# LPDDR4_SDRAM_2.net
KiCad netlist of a schematic drawn in Altium Designer
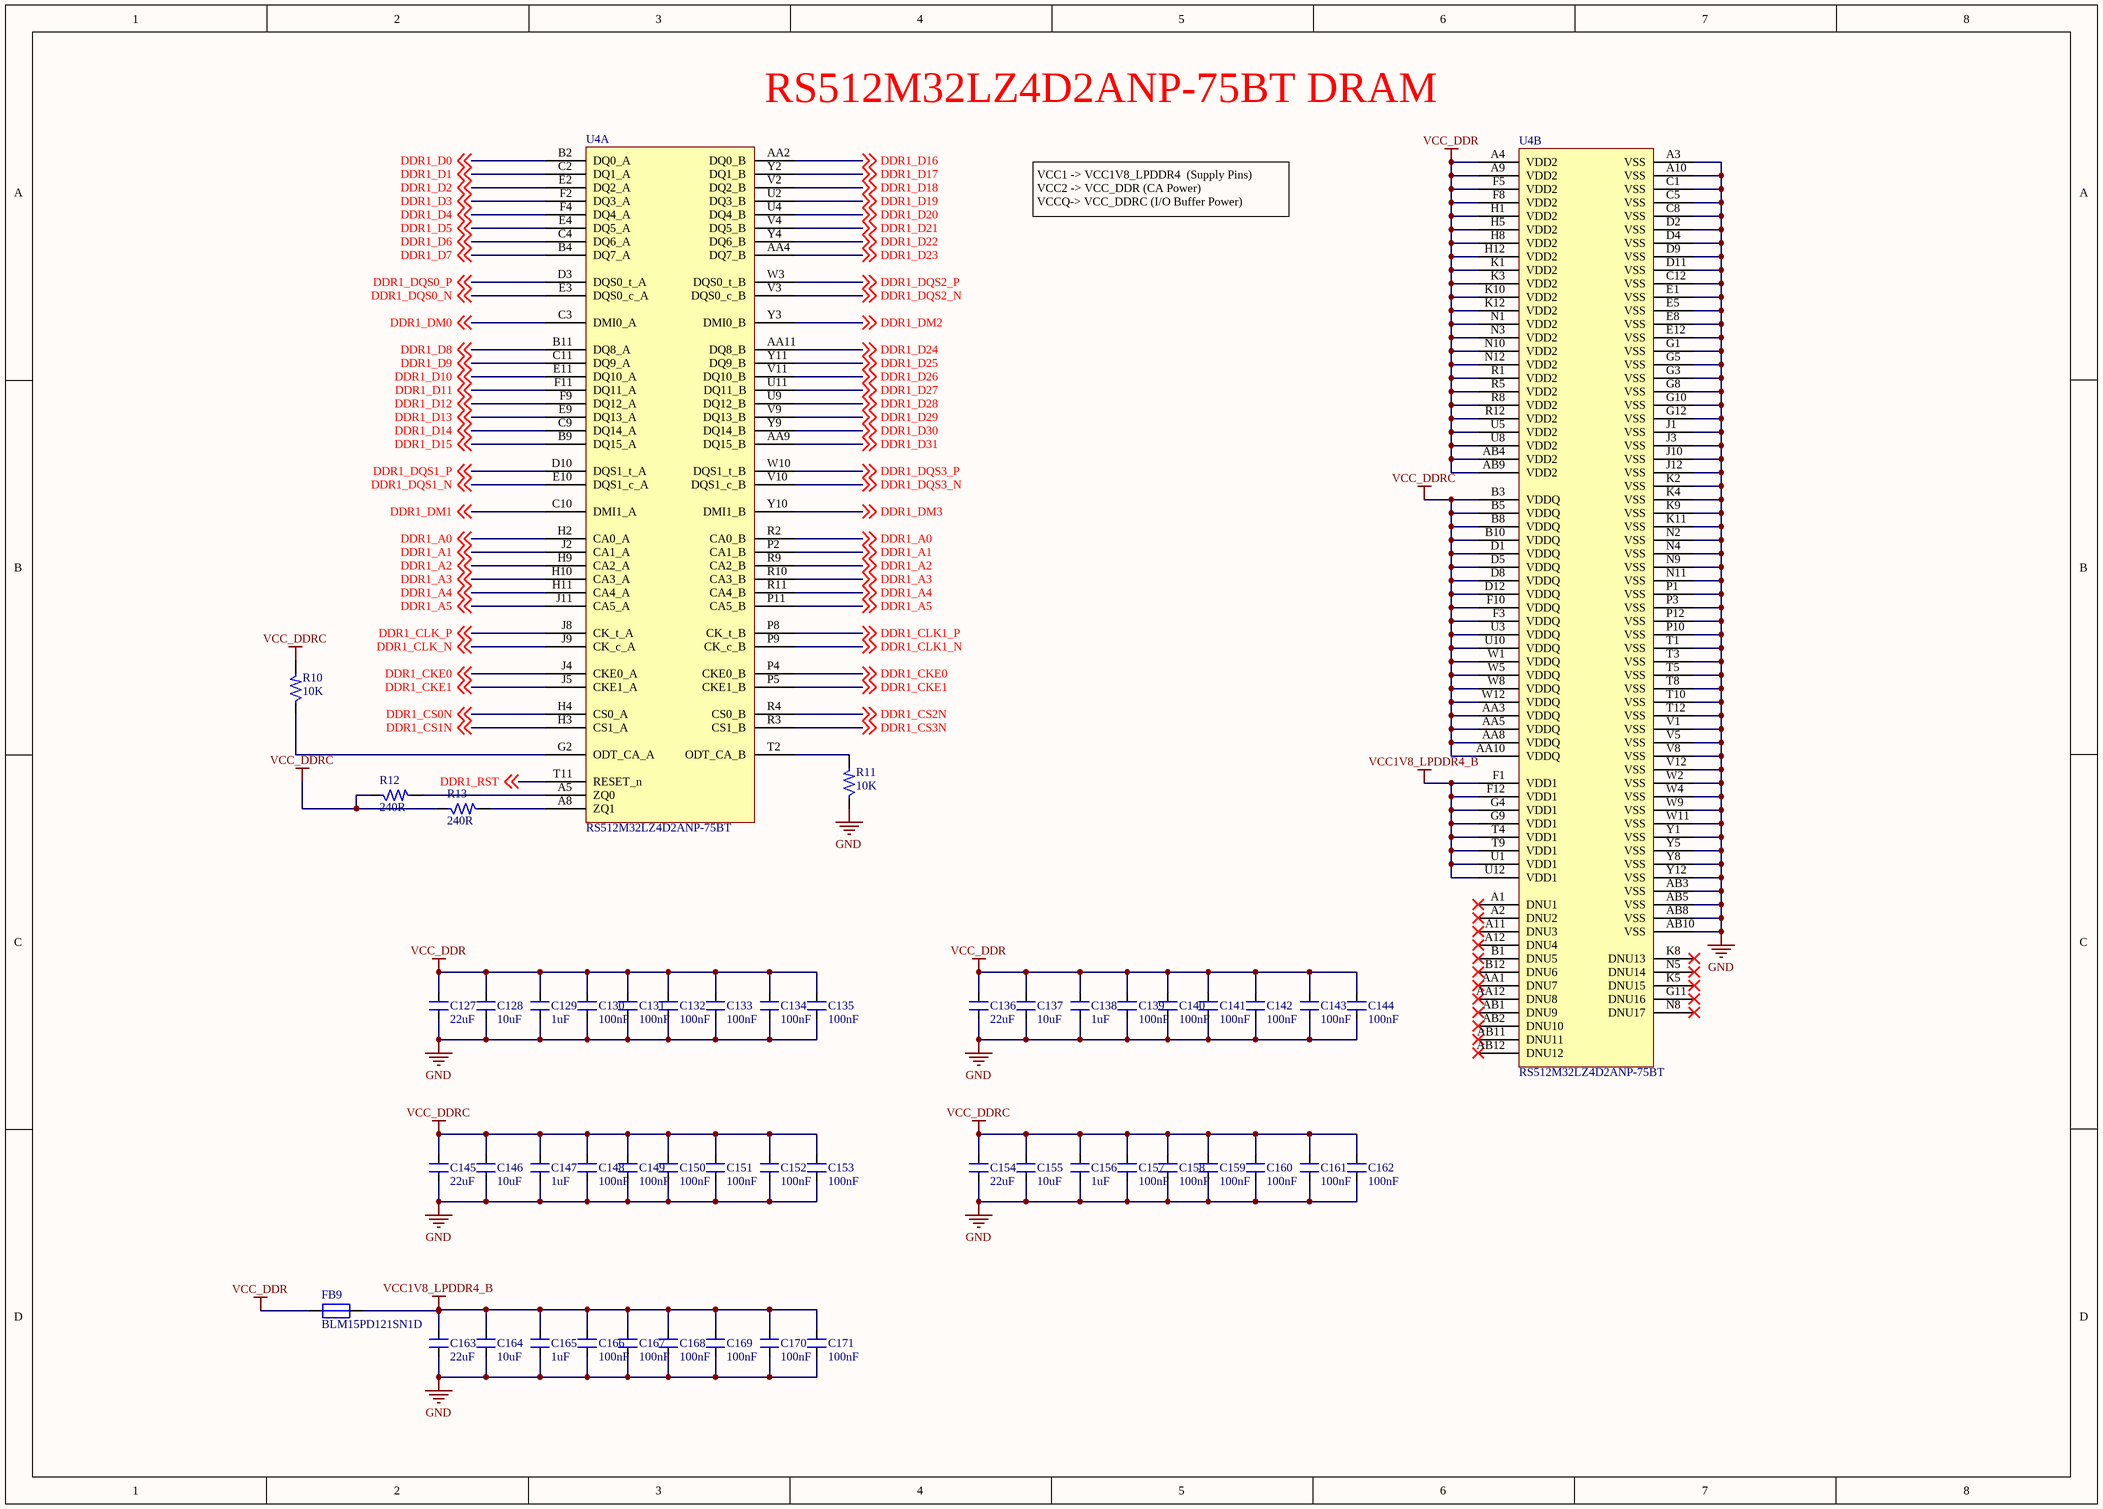
[diagram p0: LPDDR4 SDRAM_2.SchDoc]

(export (version "E")
  (design (tool "Eeschema 10.0.6"))
  (components
    (comp (ref "C127")
      (value "22uF")
      (footprint "CAP_0402")
      (description "22µF ±20% 6.3V Ceramic Capacitor X5R 0402 (1005 Metric)")
      (fields
        (field (name "MANUFACTURER") "Murata Electronics")
        (field (name "MANUFACTURER PART NUMBER") "CL05A226MQ5N6J8")
      )
      (libsource (lib "RK3399 _Module_Intlib") (part "CAP_22uF-6.3V-20%-0402"))
    )
    (comp (ref "C128")
      (value "10uF")
      (footprint "CAP_0402")
      (description "10µF ±20% 10V Ceramic Capacitor X5R 0402 (1005 Metric)")
      (fields
        (field (name "MANUFACTURER PART NUMBER") "CL05A106MP5NUNC")
        (field (name "MANUFACTURER") "Samsung Electro-Mechanics")
      )
      (libsource (lib "RK3399 _Module_Schlib") (part "CAP_10uF-10V-20%-0402"))
    )
    (comp (ref "C129")
      (value "1uF")
      (footprint "CAP_0201")
      (description "1µF ±20% 16V Ceramic Capacitor X5R 0201 (0603 Metric)")
      (fields
        (field (name "MANUFACTURER") "Samsung Electro-Mechanics")
        (field (name "MANUFACTURER PART NUMBER") "CL03A105MO3NRNH")
      )
      (libsource (lib "RK3399 _Module_Intlib") (part "CAP_1uF-16V-10%-0201"))
    )
    (comp (ref "C130")
      (value "100nF")
      (footprint "CAP_0201")
      (description "0.1µF ±10% 25V Ceramic Capacitor X5R 0201 (0603 Metric)")
      (fields
        (field (name "MANUFACTURER") "TDK Corporation")
        (field (name "MANUFACTURER PART NUMBER") "C0603X5R1E104K030BB")
      )
      (libsource (lib "RK3399 _Module_Intlib") (part "CAP_100nF-25V-10%-0201"))
    )
    (comp (ref "C131")
      (value "100nF")
      (footprint "CAP_0201")
      (description "0.1µF ±10% 25V Ceramic Capacitor X5R 0201 (0603 Metric)")
      (fields
        (field (name "MANUFACTURER") "TDK Corporation")
        (field (name "MANUFACTURER PART NUMBER") "C0603X5R1E104K030BB")
      )
      (libsource (lib "RK3399 _Module_Intlib") (part "CAP_100nF-25V-10%-0201"))
    )
    (comp (ref "C132")
      (value "100nF")
      (footprint "CAP_0201")
      (description "0.1µF ±10% 25V Ceramic Capacitor X5R 0201 (0603 Metric)")
      (fields
        (field (name "MANUFACTURER") "TDK Corporation")
        (field (name "MANUFACTURER PART NUMBER") "C0603X5R1E104K030BB")
      )
      (libsource (lib "RK3399 _Module_Intlib") (part "CAP_100nF-25V-10%-0201"))
    )
    (comp (ref "C133")
      (value "100nF")
      (footprint "CAP_0201")
      (description "0.1µF ±10% 25V Ceramic Capacitor X5R 0201 (0603 Metric)")
      (fields
        (field (name "MANUFACTURER") "TDK Corporation")
        (field (name "MANUFACTURER PART NUMBER") "C0603X5R1E104K030BB")
      )
      (libsource (lib "RK3399 _Module_Intlib") (part "CAP_100nF-25V-10%-0201"))
    )
    (comp (ref "C134")
      (value "100nF")
      (footprint "CAP_0201")
      (description "0.1µF ±10% 25V Ceramic Capacitor X5R 0201 (0603 Metric)")
      (fields
        (field (name "MANUFACTURER") "TDK Corporation")
        (field (name "MANUFACTURER PART NUMBER") "C0603X5R1E104K030BB")
      )
      (libsource (lib "RK3399 _Module_Intlib") (part "CAP_100nF-25V-10%-0201"))
    )
    (comp (ref "C135")
      (value "100nF")
      (footprint "CAP_0201")
      (description "0.1µF ±10% 25V Ceramic Capacitor X5R 0201 (0603 Metric)")
      (fields
        (field (name "MANUFACTURER") "TDK Corporation")
        (field (name "MANUFACTURER PART NUMBER") "C0603X5R1E104K030BB")
      )
      (libsource (lib "RK3399 _Module_Intlib") (part "CAP_100nF-25V-10%-0201"))
    )
    (comp (ref "C136")
      (value "22uF")
      (footprint "CAP_0402")
      (description "22µF ±20% 6.3V Ceramic Capacitor X5R 0402 (1005 Metric)")
      (fields
        (field (name "MANUFACTURER") "Murata Electronics")
        (field (name "MANUFACTURER PART NUMBER") "CL05A226MQ5N6J8")
      )
      (libsource (lib "RK3399 _Module_Intlib") (part "CAP_22uF-6.3V-20%-0402"))
    )
    (comp (ref "C137")
      (value "10uF")
      (footprint "CAP_0402")
      (description "10µF ±20% 10V Ceramic Capacitor X5R 0402 (1005 Metric)")
      (fields
        (field (name "MANUFACTURER PART NUMBER") "CL05A106MP5NUNC")
        (field (name "MANUFACTURER") "Samsung Electro-Mechanics")
      )
      (libsource (lib "RK3399 _Module_Schlib") (part "CAP_10uF-10V-20%-0402"))
    )
    (comp (ref "C138")
      (value "1uF")
      (footprint "CAP_0201")
      (description "1µF ±20% 16V Ceramic Capacitor X5R 0201 (0603 Metric)")
      (fields
        (field (name "MANUFACTURER") "Samsung Electro-Mechanics")
        (field (name "MANUFACTURER PART NUMBER") "CL03A105MO3NRNH")
      )
      (libsource (lib "RK3399 _Module_Intlib") (part "CAP_1uF-16V-10%-0201"))
    )
    (comp (ref "C139")
      (value "100nF")
      (footprint "CAP_0201")
      (description "0.1µF ±10% 25V Ceramic Capacitor X5R 0201 (0603 Metric)")
      (fields
        (field (name "MANUFACTURER") "TDK Corporation")
        (field (name "MANUFACTURER PART NUMBER") "C0603X5R1E104K030BB")
      )
      (libsource (lib "RK3399 _Module_Intlib") (part "CAP_100nF-25V-10%-0201"))
    )
    (comp (ref "C140")
      (value "100nF")
      (footprint "CAP_0201")
      (description "0.1µF ±10% 25V Ceramic Capacitor X5R 0201 (0603 Metric)")
      (fields
        (field (name "MANUFACTURER") "TDK Corporation")
        (field (name "MANUFACTURER PART NUMBER") "C0603X5R1E104K030BB")
      )
      (libsource (lib "RK3399 _Module_Intlib") (part "CAP_100nF-25V-10%-0201"))
    )
    (comp (ref "C141")
      (value "100nF")
      (footprint "CAP_0201")
      (description "0.1µF ±10% 25V Ceramic Capacitor X5R 0201 (0603 Metric)")
      (fields
        (field (name "MANUFACTURER") "TDK Corporation")
        (field (name "MANUFACTURER PART NUMBER") "C0603X5R1E104K030BB")
      )
      (libsource (lib "RK3399 _Module_Intlib") (part "CAP_100nF-25V-10%-0201"))
    )
    (comp (ref "C142")
      (value "100nF")
      (footprint "CAP_0201")
      (description "0.1µF ±10% 25V Ceramic Capacitor X5R 0201 (0603 Metric)")
      (fields
        (field (name "MANUFACTURER") "TDK Corporation")
        (field (name "MANUFACTURER PART NUMBER") "C0603X5R1E104K030BB")
      )
      (libsource (lib "RK3399 _Module_Intlib") (part "CAP_100nF-25V-10%-0201"))
    )
    (comp (ref "C143")
      (value "100nF")
      (footprint "CAP_0201")
      (description "0.1µF ±10% 25V Ceramic Capacitor X5R 0201 (0603 Metric)")
      (fields
        (field (name "MANUFACTURER") "TDK Corporation")
        (field (name "MANUFACTURER PART NUMBER") "C0603X5R1E104K030BB")
      )
      (libsource (lib "RK3399 _Module_Intlib") (part "CAP_100nF-25V-10%-0201"))
    )
    (comp (ref "C144")
      (value "100nF")
      (footprint "CAP_0201")
      (description "0.1µF ±10% 25V Ceramic Capacitor X5R 0201 (0603 Metric)")
      (fields
        (field (name "MANUFACTURER") "TDK Corporation")
        (field (name "MANUFACTURER PART NUMBER") "C0603X5R1E104K030BB")
      )
      (libsource (lib "RK3399 _Module_Intlib") (part "CAP_100nF-25V-10%-0201"))
    )
    (comp (ref "C145")
      (value "22uF")
      (footprint "CAP_0402")
      (description "22µF ±20% 6.3V Ceramic Capacitor X5R 0402 (1005 Metric)")
      (fields
        (field (name "MANUFACTURER") "Murata Electronics")
        (field (name "MANUFACTURER PART NUMBER") "CL05A226MQ5N6J8")
      )
      (libsource (lib "RK3399 _Module_Intlib") (part "CAP_22uF-6.3V-20%-0402"))
    )
    (comp (ref "C146")
      (value "10uF")
      (footprint "CAP_0402")
      (description "10µF ±20% 10V Ceramic Capacitor X5R 0402 (1005 Metric)")
      (fields
        (field (name "MANUFACTURER PART NUMBER") "CL05A106MP5NUNC")
        (field (name "MANUFACTURER") "Samsung Electro-Mechanics")
      )
      (libsource (lib "RK3399 _Module_Schlib") (part "CAP_10uF-10V-20%-0402"))
    )
    (comp (ref "C147")
      (value "1uF")
      (footprint "CAP_0201")
      (description "1µF ±20% 16V Ceramic Capacitor X5R 0201 (0603 Metric)")
      (fields
        (field (name "MANUFACTURER") "Samsung Electro-Mechanics")
        (field (name "MANUFACTURER PART NUMBER") "CL03A105MO3NRNH")
      )
      (libsource (lib "RK3399 _Module_Intlib") (part "CAP_1uF-16V-10%-0201"))
    )
    (comp (ref "C148")
      (value "100nF")
      (footprint "CAP_0201")
      (description "0.1µF ±10% 25V Ceramic Capacitor X5R 0201 (0603 Metric)")
      (fields
        (field (name "MANUFACTURER") "TDK Corporation")
        (field (name "MANUFACTURER PART NUMBER") "C0603X5R1E104K030BB")
      )
      (libsource (lib "RK3399 _Module_Intlib") (part "CAP_100nF-25V-10%-0201"))
    )
    (comp (ref "C149")
      (value "100nF")
      (footprint "CAP_0201")
      (description "0.1µF ±10% 25V Ceramic Capacitor X5R 0201 (0603 Metric)")
      (fields
        (field (name "MANUFACTURER") "TDK Corporation")
        (field (name "MANUFACTURER PART NUMBER") "C0603X5R1E104K030BB")
      )
      (libsource (lib "RK3399 _Module_Intlib") (part "CAP_100nF-25V-10%-0201"))
    )
    (comp (ref "C150")
      (value "100nF")
      (footprint "CAP_0201")
      (description "0.1µF ±10% 25V Ceramic Capacitor X5R 0201 (0603 Metric)")
      (fields
        (field (name "MANUFACTURER") "TDK Corporation")
        (field (name "MANUFACTURER PART NUMBER") "C0603X5R1E104K030BB")
      )
      (libsource (lib "RK3399 _Module_Intlib") (part "CAP_100nF-25V-10%-0201"))
    )
    (comp (ref "C151")
      (value "100nF")
      (footprint "CAP_0201")
      (description "0.1µF ±10% 25V Ceramic Capacitor X5R 0201 (0603 Metric)")
      (fields
        (field (name "MANUFACTURER") "TDK Corporation")
        (field (name "MANUFACTURER PART NUMBER") "C0603X5R1E104K030BB")
      )
      (libsource (lib "RK3399 _Module_Intlib") (part "CAP_100nF-25V-10%-0201"))
    )
    (comp (ref "C152")
      (value "100nF")
      (footprint "CAP_0201")
      (description "0.1µF ±10% 25V Ceramic Capacitor X5R 0201 (0603 Metric)")
      (fields
        (field (name "MANUFACTURER") "TDK Corporation")
        (field (name "MANUFACTURER PART NUMBER") "C0603X5R1E104K030BB")
      )
      (libsource (lib "RK3399 _Module_Intlib") (part "CAP_100nF-25V-10%-0201"))
    )
    (comp (ref "C153")
      (value "100nF")
      (footprint "CAP_0201")
      (description "0.1µF ±10% 25V Ceramic Capacitor X5R 0201 (0603 Metric)")
      (fields
        (field (name "MANUFACTURER") "TDK Corporation")
        (field (name "MANUFACTURER PART NUMBER") "C0603X5R1E104K030BB")
      )
      (libsource (lib "RK3399 _Module_Intlib") (part "CAP_100nF-25V-10%-0201"))
    )
    (comp (ref "C154")
      (value "22uF")
      (footprint "CAP_0402")
      (description "22µF ±20% 6.3V Ceramic Capacitor X5R 0402 (1005 Metric)")
      (fields
        (field (name "MANUFACTURER") "Murata Electronics")
        (field (name "MANUFACTURER PART NUMBER") "CL05A226MQ5N6J8")
      )
      (libsource (lib "RK3399 _Module_Intlib") (part "CAP_22uF-6.3V-20%-0402"))
    )
    (comp (ref "C155")
      (value "10uF")
      (footprint "CAP_0402")
      (description "10µF ±20% 10V Ceramic Capacitor X5R 0402 (1005 Metric)")
      (fields
        (field (name "MANUFACTURER PART NUMBER") "CL05A106MP5NUNC")
        (field (name "MANUFACTURER") "Samsung Electro-Mechanics")
      )
      (libsource (lib "RK3399 _Module_Schlib") (part "CAP_10uF-10V-20%-0402"))
    )
    (comp (ref "C156")
      (value "1uF")
      (footprint "CAP_0201")
      (description "1µF ±20% 16V Ceramic Capacitor X5R 0201 (0603 Metric)")
      (fields
        (field (name "MANUFACTURER") "Samsung Electro-Mechanics")
        (field (name "MANUFACTURER PART NUMBER") "CL03A105MO3NRNH")
      )
      (libsource (lib "RK3399 _Module_Intlib") (part "CAP_1uF-16V-10%-0201"))
    )
    (comp (ref "C157")
      (value "100nF")
      (footprint "CAP_0201")
      (description "0.1µF ±10% 25V Ceramic Capacitor X5R 0201 (0603 Metric)")
      (fields
        (field (name "MANUFACTURER") "TDK Corporation")
        (field (name "MANUFACTURER PART NUMBER") "C0603X5R1E104K030BB")
      )
      (libsource (lib "RK3399 _Module_Intlib") (part "CAP_100nF-25V-10%-0201"))
    )
    (comp (ref "C158")
      (value "100nF")
      (footprint "CAP_0201")
      (description "0.1µF ±10% 25V Ceramic Capacitor X5R 0201 (0603 Metric)")
      (fields
        (field (name "MANUFACTURER") "TDK Corporation")
        (field (name "MANUFACTURER PART NUMBER") "C0603X5R1E104K030BB")
      )
      (libsource (lib "RK3399 _Module_Intlib") (part "CAP_100nF-25V-10%-0201"))
    )
    (comp (ref "C159")
      (value "100nF")
      (footprint "CAP_0201")
      (description "0.1µF ±10% 25V Ceramic Capacitor X5R 0201 (0603 Metric)")
      (fields
        (field (name "MANUFACTURER") "TDK Corporation")
        (field (name "MANUFACTURER PART NUMBER") "C0603X5R1E104K030BB")
      )
      (libsource (lib "RK3399 _Module_Intlib") (part "CAP_100nF-25V-10%-0201"))
    )
    (comp (ref "C160")
      (value "100nF")
      (footprint "CAP_0201")
      (description "0.1µF ±10% 25V Ceramic Capacitor X5R 0201 (0603 Metric)")
      (fields
        (field (name "MANUFACTURER") "TDK Corporation")
        (field (name "MANUFACTURER PART NUMBER") "C0603X5R1E104K030BB")
      )
      (libsource (lib "RK3399 _Module_Intlib") (part "CAP_100nF-25V-10%-0201"))
    )
    (comp (ref "C161")
      (value "100nF")
      (footprint "CAP_0201")
      (description "0.1µF ±10% 25V Ceramic Capacitor X5R 0201 (0603 Metric)")
      (fields
        (field (name "MANUFACTURER") "TDK Corporation")
        (field (name "MANUFACTURER PART NUMBER") "C0603X5R1E104K030BB")
      )
      (libsource (lib "RK3399 _Module_Intlib") (part "CAP_100nF-25V-10%-0201"))
    )
    (comp (ref "C162")
      (value "100nF")
      (footprint "CAP_0201")
      (description "0.1µF ±10% 25V Ceramic Capacitor X5R 0201 (0603 Metric)")
      (fields
        (field (name "MANUFACTURER") "TDK Corporation")
        (field (name "MANUFACTURER PART NUMBER") "C0603X5R1E104K030BB")
      )
      (libsource (lib "RK3399 _Module_Intlib") (part "CAP_100nF-25V-10%-0201"))
    )
    (comp (ref "C163")
      (value "22uF")
      (footprint "CAP_0402")
      (description "22µF ±20% 6.3V Ceramic Capacitor X5R 0402 (1005 Metric)")
      (fields
        (field (name "MANUFACTURER") "Murata Electronics")
        (field (name "MANUFACTURER PART NUMBER") "CL05A226MQ5N6J8")
      )
      (libsource (lib "RK3399 _Module_Intlib") (part "CAP_22uF-6.3V-20%-0402"))
    )
    (comp (ref "C164")
      (value "10uF")
      (footprint "CAP_0402")
      (description "10µF ±20% 10V Ceramic Capacitor X5R 0402 (1005 Metric)")
      (fields
        (field (name "MANUFACTURER PART NUMBER") "CL05A106MP5NUNC")
        (field (name "MANUFACTURER") "Samsung Electro-Mechanics")
      )
      (libsource (lib "RK3399 _Module_Schlib") (part "CAP_10uF-10V-20%-0402"))
    )
    (comp (ref "C165")
      (value "1uF")
      (footprint "CAP_0201")
      (description "1µF ±20% 16V Ceramic Capacitor X5R 0201 (0603 Metric)")
      (fields
        (field (name "MANUFACTURER") "Samsung Electro-Mechanics")
        (field (name "MANUFACTURER PART NUMBER") "CL03A105MO3NRNH")
      )
      (libsource (lib "RK3399 _Module_Intlib") (part "CAP_1uF-16V-10%-0201"))
    )
    (comp (ref "C166")
      (value "100nF")
      (footprint "CAP_0201")
      (description "0.1µF ±10% 25V Ceramic Capacitor X5R 0201 (0603 Metric)")
      (fields
        (field (name "MANUFACTURER") "TDK Corporation")
        (field (name "MANUFACTURER PART NUMBER") "C0603X5R1E104K030BB")
      )
      (libsource (lib "RK3399 _Module_Intlib") (part "CAP_100nF-25V-10%-0201"))
    )
    (comp (ref "C167")
      (value "100nF")
      (footprint "CAP_0201")
      (description "0.1µF ±10% 25V Ceramic Capacitor X5R 0201 (0603 Metric)")
      (fields
        (field (name "MANUFACTURER") "TDK Corporation")
        (field (name "MANUFACTURER PART NUMBER") "C0603X5R1E104K030BB")
      )
      (libsource (lib "RK3399 _Module_Intlib") (part "CAP_100nF-25V-10%-0201"))
    )
    (comp (ref "C168")
      (value "100nF")
      (footprint "CAP_0201")
      (description "0.1µF ±10% 25V Ceramic Capacitor X5R 0201 (0603 Metric)")
      (fields
        (field (name "MANUFACTURER") "TDK Corporation")
        (field (name "MANUFACTURER PART NUMBER") "C0603X5R1E104K030BB")
      )
      (libsource (lib "RK3399 _Module_Intlib") (part "CAP_100nF-25V-10%-0201"))
    )
    (comp (ref "C169")
      (value "100nF")
      (footprint "CAP_0201")
      (description "0.1µF ±10% 25V Ceramic Capacitor X5R 0201 (0603 Metric)")
      (fields
        (field (name "MANUFACTURER") "TDK Corporation")
        (field (name "MANUFACTURER PART NUMBER") "C0603X5R1E104K030BB")
      )
      (libsource (lib "RK3399 _Module_Intlib") (part "CAP_100nF-25V-10%-0201"))
    )
    (comp (ref "C170")
      (value "100nF")
      (footprint "CAP_0201")
      (description "0.1µF ±10% 25V Ceramic Capacitor X5R 0201 (0603 Metric)")
      (fields
        (field (name "MANUFACTURER") "TDK Corporation")
        (field (name "MANUFACTURER PART NUMBER") "C0603X5R1E104K030BB")
      )
      (libsource (lib "RK3399 _Module_Intlib") (part "CAP_100nF-25V-10%-0201"))
    )
    (comp (ref "C171")
      (value "100nF")
      (footprint "CAP_0201")
      (description "0.1µF ±10% 25V Ceramic Capacitor X5R 0201 (0603 Metric)")
      (fields
        (field (name "MANUFACTURER") "TDK Corporation")
        (field (name "MANUFACTURER PART NUMBER") "C0603X5R1E104K030BB")
      )
      (libsource (lib "RK3399 _Module_Intlib") (part "CAP_100nF-25V-10%-0201"))
    )
    (comp (ref "FB9")
      (value "BLM15PD121SN1D")
      (footprint "RES_0402")
      (description "120 Ohms @ 100MHz 1 Power Line Ferrite Bead 0402 (1005 Metric) 1.3A 90mOhm")
      (fields (field (name "MANUFACTURER") "Murata Electronics"))
      (libsource (lib "RK3399 _Module_Schlib") (part "FB_120R-1.3A-100Mhz-0402"))
    )
    (comp (ref "R10")
      (value "10K")
      (footprint "RES_0201")
      (description "10 kOhms ±1% 0.05W, 1/20W Chip Resistor 0201 (0603 Metric) Thick Film")
      (fields
        (field (name "MANUFACTURER") "Stackpole Electronics Inc")
        (field (name "MANUFACTURER PART NUMBER") "RMCF0201FT10K0")
      )
      (libsource (lib "RK3399 _Module_Intlib") (part "RES_10K-0.05W-1%-0201"))
    )
    (comp (ref "R11")
      (value "10K")
      (footprint "RES_0201")
      (description "10 kOhms ±1% 0.05W, 1/20W Chip Resistor 0201 (0603 Metric) Thick Film")
      (fields
        (field (name "MANUFACTURER") "Stackpole Electronics Inc")
        (field (name "MANUFACTURER PART NUMBER") "RMCF0201FT10K0")
      )
      (libsource (lib "RK3399 _Module_Intlib") (part "RES_10K-0.05W-1%-0201"))
    )
    (comp (ref "R12")
      (value "240R")
      (footprint "RES_0201")
      (description "240 Ohms ±1% 0.05W, 1/20W Chip Resistor 0201 (0603 Metric) Thick Film")
      (fields
        (field (name "MANUFACTURER") "Yageo")
        (field (name "MANUFACTURER PART NUMBER") "RC0201FR-07240RL")
      )
      (libsource (lib "RK3399 _Module_Intlib") (part "RES_240R-0.05W-1%-0201"))
    )
    (comp (ref "R13")
      (value "240R")
      (footprint "RES_0201")
      (description "240 Ohms ±1% 0.05W, 1/20W Chip Resistor 0201 (0603 Metric) Thick Film")
      (fields
        (field (name "MANUFACTURER") "Yageo")
        (field (name "MANUFACTURER PART NUMBER") "RC0201FR-07240RL")
      )
      (libsource (lib "RK3399 _Module_Intlib") (part "RES_240R-0.05W-1%-0201"))
    )
    (comp (ref "U4")
      (value "RS512M32LZ4D2ANP-75BT")
      (footprint "FBGA200_SMD")
      (fields (field (name "MANUFACTURER") "RAYSON"))
      (libsource (lib "RK3399 _Module_Schlib") (part "IC_RS512M32LZ4D2ANP-75BT"))
    )
  )
  (nets
    (net (code "1") (name "DDR1_A0") (class "Default")
      (node (ref "U4") (pin "H2") (pinfunction "CA0_A_H2") (pintype "passive"))
      (node (ref "U4") (pin "R2") (pinfunction "CA0_B_R2") (pintype "passive"))
    )
    (net (code "2") (name "DDR1_A1") (class "Default")
      (node (ref "U4") (pin "J2") (pinfunction "CA1_A_J2") (pintype "passive"))
      (node (ref "U4") (pin "P2") (pinfunction "CA1_B_P2") (pintype "passive"))
    )
    (net (code "3") (name "DDR1_A2") (class "Default")
      (node (ref "U4") (pin "H9") (pinfunction "CA2_A_H9") (pintype "passive"))
      (node (ref "U4") (pin "R9") (pinfunction "CA2_B_R9") (pintype "passive"))
    )
    (net (code "4") (name "DDR1_A3") (class "Default")
      (node (ref "U4") (pin "H10") (pinfunction "CA3_A_H10") (pintype "passive"))
      (node (ref "U4") (pin "R10") (pinfunction "CA3_B_R10") (pintype "passive"))
    )
    (net (code "5") (name "DDR1_A4") (class "Default")
      (node (ref "U4") (pin "H11") (pinfunction "CA4_A_H11") (pintype "passive"))
      (node (ref "U4") (pin "R11") (pinfunction "CA4_B_R11") (pintype "passive"))
    )
    (net (code "6") (name "DDR1_A5") (class "Default")
      (node (ref "U4") (pin "J11") (pinfunction "CA5_A_J11") (pintype "passive"))
      (node (ref "U4") (pin "P11") (pinfunction "CA5_B_P11") (pintype "passive"))
    )
    (net (code "7") (name "DDR1_CKE0") (class "Default")
      (node (ref "U4") (pin "J4") (pinfunction "CKE0_A_J4") (pintype "passive"))
      (node (ref "U4") (pin "P4") (pinfunction "CKE0_B_P4") (pintype "passive"))
    )
    (net (code "8") (name "DDR1_CKE1") (class "Default")
      (node (ref "U4") (pin "J5") (pinfunction "CKE1_A_J5") (pintype "passive"))
      (node (ref "U4") (pin "P5") (pinfunction "CKE1_B_P5") (pintype "passive"))
    )
    (net (code "9") (name "DDR1_CLK1_N") (class "Default")
      (node (ref "U4") (pin "P9") (pinfunction "CK_c_B_P9") (pintype "passive"))
    )
    (net (code "10") (name "DDR1_CLK1_P") (class "Default")
      (node (ref "U4") (pin "P8") (pinfunction "CK_t_B_P8") (pintype "passive"))
    )
    (net (code "11") (name "DDR1_CLK_N") (class "Default")
      (node (ref "U4") (pin "J9") (pinfunction "CK_c_A_J9") (pintype "passive"))
    )
    (net (code "12") (name "DDR1_CLK_P") (class "Default")
      (node (ref "U4") (pin "J8") (pinfunction "CK_t_A_J8") (pintype "passive"))
    )
    (net (code "13") (name "DDR1_CS0N") (class "Default")
      (node (ref "U4") (pin "H4") (pinfunction "CS0_A_H4") (pintype "passive"))
    )
    (net (code "14") (name "DDR1_CS1N") (class "Default")
      (node (ref "U4") (pin "H3") (pinfunction "CS1_A_H3") (pintype "passive"))
    )
    (net (code "15") (name "DDR1_CS2N") (class "Default")
      (node (ref "U4") (pin "R4") (pinfunction "CS0_B_R4") (pintype "passive"))
    )
    (net (code "16") (name "DDR1_CS3N") (class "Default")
      (node (ref "U4") (pin "R3") (pinfunction "CS1_B_R3") (pintype "passive"))
    )
    (net (code "17") (name "DDR1_D0") (class "Default")
      (node (ref "U4") (pin "B2") (pinfunction "DQ0_A_B2") (pintype "passive"))
    )
    (net (code "18") (name "DDR1_D1") (class "Default")
      (node (ref "U4") (pin "C2") (pinfunction "DQ1_A_C2") (pintype "passive"))
    )
    (net (code "19") (name "DDR1_D2") (class "Default")
      (node (ref "U4") (pin "E2") (pinfunction "DQ2_A_E2") (pintype "passive"))
    )
    (net (code "20") (name "DDR1_D3") (class "Default")
      (node (ref "U4") (pin "F2") (pinfunction "DQ3_A_F2") (pintype "passive"))
    )
    (net (code "21") (name "DDR1_D4") (class "Default")
      (node (ref "U4") (pin "F4") (pinfunction "DQ4_A_F4") (pintype "passive"))
    )
    (net (code "22") (name "DDR1_D5") (class "Default")
      (node (ref "U4") (pin "E4") (pinfunction "DQ5_A_E4") (pintype "passive"))
    )
    (net (code "23") (name "DDR1_D6") (class "Default")
      (node (ref "U4") (pin "C4") (pinfunction "DQ6_A_C4") (pintype "passive"))
    )
    (net (code "24") (name "DDR1_D7") (class "Default")
      (node (ref "U4") (pin "B4") (pinfunction "DQ7_A_B4") (pintype "passive"))
    )
    (net (code "25") (name "DDR1_D8") (class "Default")
      (node (ref "U4") (pin "B11") (pinfunction "DQ8_A_B11") (pintype "passive"))
    )
    (net (code "26") (name "DDR1_D9") (class "Default")
      (node (ref "U4") (pin "C11") (pinfunction "DQ9_A_C11") (pintype "passive"))
    )
    (net (code "27") (name "DDR1_D10") (class "Default")
      (node (ref "U4") (pin "E11") (pinfunction "DQ10_A_E11") (pintype "passive"))
    )
    (net (code "28") (name "DDR1_D11") (class "Default")
      (node (ref "U4") (pin "F11") (pinfunction "DQ11_A_F11") (pintype "passive"))
    )
    (net (code "29") (name "DDR1_D12") (class "Default")
      (node (ref "U4") (pin "F9") (pinfunction "DQ12_A_F9") (pintype "passive"))
    )
    (net (code "30") (name "DDR1_D13") (class "Default")
      (node (ref "U4") (pin "E9") (pinfunction "DQ13_A_E9") (pintype "passive"))
    )
    (net (code "31") (name "DDR1_D14") (class "Default")
      (node (ref "U4") (pin "C9") (pinfunction "DQ14_A_C9") (pintype "passive"))
    )
    (net (code "32") (name "DDR1_D15") (class "Default")
      (node (ref "U4") (pin "B9") (pinfunction "DQ15_A_B9") (pintype "passive"))
    )
    (net (code "33") (name "DDR1_D16") (class "Default")
      (node (ref "U4") (pin "AA2") (pinfunction "DQ0_B_AA2") (pintype "passive"))
    )
    (net (code "34") (name "DDR1_D17") (class "Default")
      (node (ref "U4") (pin "Y2") (pinfunction "DQ1_B_Y2") (pintype "passive"))
    )
    (net (code "35") (name "DDR1_D18") (class "Default")
      (node (ref "U4") (pin "V2") (pinfunction "DQ2_B_V2") (pintype "passive"))
    )
    (net (code "36") (name "DDR1_D19") (class "Default")
      (node (ref "U4") (pin "U2") (pinfunction "DQ3_B_U2") (pintype "passive"))
    )
    (net (code "37") (name "DDR1_D20") (class "Default")
      (node (ref "U4") (pin "U4") (pinfunction "DQ4_B_U4") (pintype "passive"))
    )
    (net (code "38") (name "DDR1_D21") (class "Default")
      (node (ref "U4") (pin "V4") (pinfunction "DQ5_B_V4") (pintype "passive"))
    )
    (net (code "39") (name "DDR1_D22") (class "Default")
      (node (ref "U4") (pin "Y4") (pinfunction "DQ6_B_Y4") (pintype "passive"))
    )
    (net (code "40") (name "DDR1_D23") (class "Default")
      (node (ref "U4") (pin "AA4") (pinfunction "DQ7_B_AA4") (pintype "passive"))
    )
    (net (code "41") (name "DDR1_D24") (class "Default")
      (node (ref "U4") (pin "AA11") (pinfunction "DQ8_B_AA11") (pintype "passive"))
    )
    (net (code "42") (name "DDR1_D25") (class "Default")
      (node (ref "U4") (pin "Y11") (pinfunction "DQ9_B_Y11") (pintype "passive"))
    )
    (net (code "43") (name "DDR1_D26") (class "Default")
      (node (ref "U4") (pin "V11") (pinfunction "DQ10_B_V11") (pintype "passive"))
    )
    (net (code "44") (name "DDR1_D27") (class "Default")
      (node (ref "U4") (pin "U11") (pinfunction "DQ11_B_U11") (pintype "passive"))
    )
    (net (code "45") (name "DDR1_D28") (class "Default")
      (node (ref "U4") (pin "U9") (pinfunction "DQ12_B_U9") (pintype "passive"))
    )
    (net (code "46") (name "DDR1_D29") (class "Default")
      (node (ref "U4") (pin "V9") (pinfunction "DQ13_B_V9") (pintype "passive"))
    )
    (net (code "47") (name "DDR1_D30") (class "Default")
      (node (ref "U4") (pin "Y9") (pinfunction "DQ14_B_Y9") (pintype "passive"))
    )
    (net (code "48") (name "DDR1_D31") (class "Default")
      (node (ref "U4") (pin "AA9") (pinfunction "DQ15_B_AA9") (pintype "passive"))
    )
    (net (code "49") (name "DDR1_DM0") (class "Default")
      (node (ref "U4") (pin "C3") (pinfunction "DMI0_A_C3") (pintype "passive"))
    )
    (net (code "50") (name "DDR1_DM1") (class "Default")
      (node (ref "U4") (pin "C10") (pinfunction "DMI1_A_C10") (pintype "passive"))
    )
    (net (code "51") (name "DDR1_DM2") (class "Default")
      (node (ref "U4") (pin "Y3") (pinfunction "DMI0_B_Y3") (pintype "passive"))
    )
    (net (code "52") (name "DDR1_DM3") (class "Default")
      (node (ref "U4") (pin "Y10") (pinfunction "DMI1_B_Y10") (pintype "passive"))
    )
    (net (code "53") (name "DDR1_DQS0_N") (class "Default")
      (node (ref "U4") (pin "E3") (pinfunction "DQS0_c_A_E3") (pintype "passive"))
    )
    (net (code "54") (name "DDR1_DQS0_P") (class "Default")
      (node (ref "U4") (pin "D3") (pinfunction "DQS0_t_A_D3") (pintype "passive"))
    )
    (net (code "55") (name "DDR1_DQS1_N") (class "Default")
      (node (ref "U4") (pin "E10") (pinfunction "DQS1_c_A_E10") (pintype "passive"))
    )
    (net (code "56") (name "DDR1_DQS1_P") (class "Default")
      (node (ref "U4") (pin "D10") (pinfunction "DQS1_t_A_D10") (pintype "passive"))
    )
    (net (code "57") (name "DDR1_DQS2_N") (class "Default")
      (node (ref "U4") (pin "V3") (pinfunction "DQS0_c_B_V3") (pintype "passive"))
    )
    (net (code "58") (name "DDR1_DQS2_P") (class "Default")
      (node (ref "U4") (pin "W3") (pinfunction "DQS0_t_B_W3") (pintype "passive"))
    )
    (net (code "59") (name "DDR1_DQS3_N") (class "Default")
      (node (ref "U4") (pin "V10") (pinfunction "DQS1_c_B_V10") (pintype "passive"))
    )
    (net (code "60") (name "DDR1_DQS3_P") (class "Default")
      (node (ref "U4") (pin "W10") (pinfunction "DQS1_t_B_W10") (pintype "passive"))
    )
    (net (code "61") (name "DDR1_RST") (class "Default")
      (node (ref "U4") (pin "T11") (pinfunction "RESET_n_T11") (pintype "passive"))
    )
    (net (code "62") (name "GND") (class "Default")
      (node (ref "C127") (pin "1") (pinfunction "1_1") (pintype "passive"))
      (node (ref "C128") (pin "1") (pinfunction "1_1") (pintype "passive"))
      (node (ref "C129") (pin "1") (pinfunction "1_1") (pintype "passive"))
      (node (ref "C130") (pin "1") (pinfunction "1_1") (pintype "passive"))
      (node (ref "C131") (pin "1") (pinfunction "1_1") (pintype "passive"))
      (node (ref "C132") (pin "1") (pinfunction "1_1") (pintype "passive"))
      (node (ref "C133") (pin "1") (pinfunction "1_1") (pintype "passive"))
      (node (ref "C134") (pin "1") (pinfunction "1_1") (pintype "passive"))
      (node (ref "C135") (pin "1") (pinfunction "1_1") (pintype "passive"))
      (node (ref "C136") (pin "1") (pinfunction "1_1") (pintype "passive"))
      (node (ref "C137") (pin "1") (pinfunction "1_1") (pintype "passive"))
      (node (ref "C138") (pin "1") (pinfunction "1_1") (pintype "passive"))
      (node (ref "C139") (pin "1") (pinfunction "1_1") (pintype "passive"))
      (node (ref "C140") (pin "1") (pinfunction "1_1") (pintype "passive"))
      (node (ref "C141") (pin "1") (pinfunction "1_1") (pintype "passive"))
      (node (ref "C142") (pin "1") (pinfunction "1_1") (pintype "passive"))
      (node (ref "C143") (pin "1") (pinfunction "1_1") (pintype "passive"))
      (node (ref "C144") (pin "1") (pinfunction "1_1") (pintype "passive"))
      (node (ref "C145") (pin "1") (pinfunction "1_1") (pintype "passive"))
      (node (ref "C146") (pin "1") (pinfunction "1_1") (pintype "passive"))
      (node (ref "C147") (pin "1") (pinfunction "1_1") (pintype "passive"))
      (node (ref "C148") (pin "1") (pinfunction "1_1") (pintype "passive"))
      (node (ref "C149") (pin "1") (pinfunction "1_1") (pintype "passive"))
      (node (ref "C150") (pin "1") (pinfunction "1_1") (pintype "passive"))
      (node (ref "C151") (pin "1") (pinfunction "1_1") (pintype "passive"))
      (node (ref "C152") (pin "1") (pinfunction "1_1") (pintype "passive"))
      (node (ref "C153") (pin "1") (pinfunction "1_1") (pintype "passive"))
      (node (ref "C154") (pin "1") (pinfunction "1_1") (pintype "passive"))
      (node (ref "C155") (pin "1") (pinfunction "1_1") (pintype "passive"))
      (node (ref "C156") (pin "1") (pinfunction "1_1") (pintype "passive"))
      (node (ref "C157") (pin "1") (pinfunction "1_1") (pintype "passive"))
      (node (ref "C158") (pin "1") (pinfunction "1_1") (pintype "passive"))
      (node (ref "C159") (pin "1") (pinfunction "1_1") (pintype "passive"))
      (node (ref "C160") (pin "1") (pinfunction "1_1") (pintype "passive"))
      (node (ref "C161") (pin "1") (pinfunction "1_1") (pintype "passive"))
      (node (ref "C162") (pin "1") (pinfunction "1_1") (pintype "passive"))
      (node (ref "C163") (pin "1") (pinfunction "1_1") (pintype "passive"))
      (node (ref "C164") (pin "1") (pinfunction "1_1") (pintype "passive"))
      (node (ref "C165") (pin "1") (pinfunction "1_1") (pintype "passive"))
      (node (ref "C166") (pin "1") (pinfunction "1_1") (pintype "passive"))
      (node (ref "C167") (pin "1") (pinfunction "1_1") (pintype "passive"))
      (node (ref "C168") (pin "1") (pinfunction "1_1") (pintype "passive"))
      (node (ref "C169") (pin "1") (pinfunction "1_1") (pintype "passive"))
      (node (ref "C170") (pin "1") (pinfunction "1_1") (pintype "passive"))
      (node (ref "C171") (pin "1") (pinfunction "1_1") (pintype "passive"))
      (node (ref "R11") (pin "1") (pinfunction "1_1") (pintype "passive"))
      (node (ref "U4") (pin "A10") (pinfunction "VSS_A10") (pintype "passive"))
      (node (ref "U4") (pin "A3") (pinfunction "VSS_A3") (pintype "passive"))
      (node (ref "U4") (pin "AB10") (pinfunction "VSS_AB10") (pintype "passive"))
      (node (ref "U4") (pin "AB3") (pinfunction "VSS_AB3") (pintype "passive"))
      (node (ref "U4") (pin "AB5") (pinfunction "VSS_AB5") (pintype "passive"))
      (node (ref "U4") (pin "AB8") (pinfunction "VSS_AB8") (pintype "passive"))
      (node (ref "U4") (pin "C1") (pinfunction "VSS_C1") (pintype "passive"))
      (node (ref "U4") (pin "C12") (pinfunction "VSS_C12") (pintype "passive"))
      (node (ref "U4") (pin "C5") (pinfunction "VSS_C5") (pintype "passive"))
      (node (ref "U4") (pin "C8") (pinfunction "VSS_C8") (pintype "passive"))
      (node (ref "U4") (pin "D11") (pinfunction "VSS_D11") (pintype "passive"))
      (node (ref "U4") (pin "D2") (pinfunction "VSS_D2") (pintype "passive"))
      (node (ref "U4") (pin "D4") (pinfunction "VSS_D4") (pintype "passive"))
      (node (ref "U4") (pin "D9") (pinfunction "VSS_D9") (pintype "passive"))
      (node (ref "U4") (pin "E1") (pinfunction "VSS_E1") (pintype "passive"))
      (node (ref "U4") (pin "E12") (pinfunction "VSS_E12") (pintype "passive"))
      (node (ref "U4") (pin "E5") (pinfunction "VSS_E5") (pintype "passive"))
      (node (ref "U4") (pin "E8") (pinfunction "VSS_E8") (pintype "passive"))
      (node (ref "U4") (pin "G1") (pinfunction "VSS_G1") (pintype "passive"))
      (node (ref "U4") (pin "G10") (pinfunction "VSS_G10") (pintype "passive"))
      (node (ref "U4") (pin "G12") (pinfunction "VSS_G12") (pintype "passive"))
      (node (ref "U4") (pin "G3") (pinfunction "VSS_G3") (pintype "passive"))
      (node (ref "U4") (pin "G5") (pinfunction "VSS_G5") (pintype "passive"))
      (node (ref "U4") (pin "G8") (pinfunction "VSS_G8") (pintype "passive"))
      (node (ref "U4") (pin "J1") (pinfunction "VSS_J1") (pintype "passive"))
      (node (ref "U4") (pin "J10") (pinfunction "VSS_J10") (pintype "passive"))
      (node (ref "U4") (pin "J12") (pinfunction "VSS_J12") (pintype "passive"))
      (node (ref "U4") (pin "J3") (pinfunction "VSS_J3") (pintype "passive"))
      (node (ref "U4") (pin "K11") (pinfunction "VSS_K11") (pintype "passive"))
      (node (ref "U4") (pin "K2") (pinfunction "VSS_K2") (pintype "passive"))
      (node (ref "U4") (pin "K4") (pinfunction "VSS_K4") (pintype "passive"))
      (node (ref "U4") (pin "K9") (pinfunction "VSS_K9") (pintype "passive"))
      (node (ref "U4") (pin "N11") (pinfunction "VSS_N11") (pintype "passive"))
      (node (ref "U4") (pin "N2") (pinfunction "VSS_N2") (pintype "passive"))
      (node (ref "U4") (pin "N4") (pinfunction "VSS_N4") (pintype "passive"))
      (node (ref "U4") (pin "N9") (pinfunction "VSS_N9") (pintype "passive"))
      (node (ref "U4") (pin "P1") (pinfunction "VSS_P1") (pintype "passive"))
      (node (ref "U4") (pin "P10") (pinfunction "VSS_P10") (pintype "passive"))
      (node (ref "U4") (pin "P12") (pinfunction "VSS_P12") (pintype "passive"))
      (node (ref "U4") (pin "P3") (pinfunction "VSS_P3") (pintype "passive"))
      (node (ref "U4") (pin "T1") (pinfunction "VSS_T1") (pintype "passive"))
      (node (ref "U4") (pin "T10") (pinfunction "VSS_T10") (pintype "passive"))
      (node (ref "U4") (pin "T12") (pinfunction "VSS_T12") (pintype "passive"))
      (node (ref "U4") (pin "T3") (pinfunction "VSS_T3") (pintype "passive"))
      (node (ref "U4") (pin "T5") (pinfunction "VSS_T5") (pintype "passive"))
      (node (ref "U4") (pin "T8") (pinfunction "VSS_T8") (pintype "passive"))
      (node (ref "U4") (pin "V1") (pinfunction "VSS_V1") (pintype "passive"))
      (node (ref "U4") (pin "V12") (pinfunction "VSS_V12") (pintype "passive"))
      (node (ref "U4") (pin "V5") (pinfunction "VSS_V5") (pintype "passive"))
      (node (ref "U4") (pin "V8") (pinfunction "VSS_V8") (pintype "passive"))
      (node (ref "U4") (pin "W11") (pinfunction "VSS_W11") (pintype "passive"))
      (node (ref "U4") (pin "W2") (pinfunction "VSS_W2") (pintype "passive"))
      (node (ref "U4") (pin "W4") (pinfunction "VSS_W4") (pintype "passive"))
      (node (ref "U4") (pin "W9") (pinfunction "VSS_W9") (pintype "passive"))
      (node (ref "U4") (pin "Y1") (pinfunction "VSS_Y1") (pintype "passive"))
      (node (ref "U4") (pin "Y12") (pinfunction "VSS_Y12") (pintype "passive"))
      (node (ref "U4") (pin "Y5") (pinfunction "VSS_Y5") (pintype "passive"))
      (node (ref "U4") (pin "Y8") (pinfunction "VSS_Y8") (pintype "passive"))
    )
    (net (code "63") (name "Net-(U4A-ODT_CA_A)") (class "Default")
      (node (ref "R10") (pin "1") (pinfunction "1_1") (pintype "passive"))
      (node (ref "U4") (pin "G2") (pinfunction "ODT_CA_A_G2") (pintype "passive"))
    )
    (net (code "64") (name "Net-(U4A-ODT_CA_B)") (class "Default")
      (node (ref "R11") (pin "2") (pinfunction "2_2") (pintype "passive"))
      (node (ref "U4") (pin "T2") (pinfunction "ODT_CA_B_T2") (pintype "passive"))
    )
    (net (code "65") (name "Net-(U4A-ZQ0)") (class "Default")
      (node (ref "R12") (pin "2") (pinfunction "2_2") (pintype "passive"))
      (node (ref "U4") (pin "A5") (pinfunction "ZQ0_A5") (pintype "passive"))
    )
    (net (code "66") (name "Net-(U4A-ZQ1)") (class "Default")
      (node (ref "R13") (pin "2") (pinfunction "2_2") (pintype "passive"))
      (node (ref "U4") (pin "A8") (pinfunction "ZQ1_A8") (pintype "passive"))
    )
    (net (code "67") (name "VCC1V8_LPDDR4_B") (class "Default")
      (node (ref "C163") (pin "2") (pinfunction "2_2") (pintype "passive"))
      (node (ref "C164") (pin "2") (pinfunction "2_2") (pintype "passive"))
      (node (ref "C165") (pin "2") (pinfunction "2_2") (pintype "passive"))
      (node (ref "C166") (pin "2") (pinfunction "2_2") (pintype "passive"))
      (node (ref "C167") (pin "2") (pinfunction "2_2") (pintype "passive"))
      (node (ref "C168") (pin "2") (pinfunction "2_2") (pintype "passive"))
      (node (ref "C169") (pin "2") (pinfunction "2_2") (pintype "passive"))
      (node (ref "C170") (pin "2") (pinfunction "2_2") (pintype "passive"))
      (node (ref "C171") (pin "2") (pinfunction "2_2") (pintype "passive"))
      (node (ref "FB9") (pin "2") (pinfunction "2_2") (pintype "passive"))
      (node (ref "U4") (pin "F1") (pinfunction "VDD1_F1") (pintype "passive"))
      (node (ref "U4") (pin "F12") (pinfunction "VDD1_F12") (pintype "passive"))
      (node (ref "U4") (pin "G4") (pinfunction "VDD1_G4") (pintype "passive"))
      (node (ref "U4") (pin "G9") (pinfunction "VDD1_G9") (pintype "passive"))
      (node (ref "U4") (pin "T4") (pinfunction "VDD1_T4") (pintype "passive"))
      (node (ref "U4") (pin "T9") (pinfunction "VDD1_T9") (pintype "passive"))
      (node (ref "U4") (pin "U1") (pinfunction "VDD1_U1") (pintype "passive"))
      (node (ref "U4") (pin "U12") (pinfunction "VDD1_U12") (pintype "passive"))
    )
    (net (code "68") (name "VCC_DDR") (class "Default")
      (node (ref "C127") (pin "2") (pinfunction "2_2") (pintype "passive"))
      (node (ref "C128") (pin "2") (pinfunction "2_2") (pintype "passive"))
      (node (ref "C129") (pin "2") (pinfunction "2_2") (pintype "passive"))
      (node (ref "C130") (pin "2") (pinfunction "2_2") (pintype "passive"))
      (node (ref "C131") (pin "2") (pinfunction "2_2") (pintype "passive"))
      (node (ref "C132") (pin "2") (pinfunction "2_2") (pintype "passive"))
      (node (ref "C133") (pin "2") (pinfunction "2_2") (pintype "passive"))
      (node (ref "C134") (pin "2") (pinfunction "2_2") (pintype "passive"))
      (node (ref "C135") (pin "2") (pinfunction "2_2") (pintype "passive"))
      (node (ref "C136") (pin "2") (pinfunction "2_2") (pintype "passive"))
      (node (ref "C137") (pin "2") (pinfunction "2_2") (pintype "passive"))
      (node (ref "C138") (pin "2") (pinfunction "2_2") (pintype "passive"))
      (node (ref "C139") (pin "2") (pinfunction "2_2") (pintype "passive"))
      (node (ref "C140") (pin "2") (pinfunction "2_2") (pintype "passive"))
      (node (ref "C141") (pin "2") (pinfunction "2_2") (pintype "passive"))
      (node (ref "C142") (pin "2") (pinfunction "2_2") (pintype "passive"))
      (node (ref "C143") (pin "2") (pinfunction "2_2") (pintype "passive"))
      (node (ref "C144") (pin "2") (pinfunction "2_2") (pintype "passive"))
      (node (ref "FB9") (pin "1") (pinfunction "1_1") (pintype "passive"))
      (node (ref "U4") (pin "A4") (pinfunction "VDD2_A4") (pintype "passive"))
      (node (ref "U4") (pin "A9") (pinfunction "VDD2_A9") (pintype "passive"))
      (node (ref "U4") (pin "AB4") (pinfunction "VDD2_AB4") (pintype "passive"))
      (node (ref "U4") (pin "AB9") (pinfunction "VDD2_AB9") (pintype "passive"))
      (node (ref "U4") (pin "F5") (pinfunction "VDD2_F5") (pintype "passive"))
      (node (ref "U4") (pin "F8") (pinfunction "VDD2_F8") (pintype "passive"))
      (node (ref "U4") (pin "H1") (pinfunction "VDD2_H1") (pintype "passive"))
      (node (ref "U4") (pin "H12") (pinfunction "VDD2_H12") (pintype "passive"))
      (node (ref "U4") (pin "H5") (pinfunction "VDD2_H5") (pintype "passive"))
      (node (ref "U4") (pin "H8") (pinfunction "VDD2_H8") (pintype "passive"))
      (node (ref "U4") (pin "K1") (pinfunction "VDD2_K1") (pintype "passive"))
      (node (ref "U4") (pin "K10") (pinfunction "VDD2_K10") (pintype "passive"))
      (node (ref "U4") (pin "K12") (pinfunction "VDD2_K12") (pintype "passive"))
      (node (ref "U4") (pin "K3") (pinfunction "VDD2_K3") (pintype "passive"))
      (node (ref "U4") (pin "N1") (pinfunction "VDD2_N1") (pintype "passive"))
      (node (ref "U4") (pin "N10") (pinfunction "VDD2_N10") (pintype "passive"))
      (node (ref "U4") (pin "N12") (pinfunction "VDD2_N12") (pintype "passive"))
      (node (ref "U4") (pin "N3") (pinfunction "VDD2_N3") (pintype "passive"))
      (node (ref "U4") (pin "R1") (pinfunction "VDD2_R1") (pintype "passive"))
      (node (ref "U4") (pin "R12") (pinfunction "VDD2_R12") (pintype "passive"))
      (node (ref "U4") (pin "R5") (pinfunction "VDD2_R5") (pintype "passive"))
      (node (ref "U4") (pin "R8") (pinfunction "VDD2_R8") (pintype "passive"))
      (node (ref "U4") (pin "U5") (pinfunction "VDD2_U5") (pintype "passive"))
      (node (ref "U4") (pin "U8") (pinfunction "VDD2_U8") (pintype "passive"))
    )
    (net (code "69") (name "VCC_DDRC") (class "Default")
      (node (ref "C145") (pin "2") (pinfunction "2_2") (pintype "passive"))
      (node (ref "C146") (pin "2") (pinfunction "2_2") (pintype "passive"))
      (node (ref "C147") (pin "2") (pinfunction "2_2") (pintype "passive"))
      (node (ref "C148") (pin "2") (pinfunction "2_2") (pintype "passive"))
      (node (ref "C149") (pin "2") (pinfunction "2_2") (pintype "passive"))
      (node (ref "C150") (pin "2") (pinfunction "2_2") (pintype "passive"))
      (node (ref "C151") (pin "2") (pinfunction "2_2") (pintype "passive"))
      (node (ref "C152") (pin "2") (pinfunction "2_2") (pintype "passive"))
      (node (ref "C153") (pin "2") (pinfunction "2_2") (pintype "passive"))
      (node (ref "C154") (pin "2") (pinfunction "2_2") (pintype "passive"))
      (node (ref "C155") (pin "2") (pinfunction "2_2") (pintype "passive"))
      (node (ref "C156") (pin "2") (pinfunction "2_2") (pintype "passive"))
      (node (ref "C157") (pin "2") (pinfunction "2_2") (pintype "passive"))
      (node (ref "C158") (pin "2") (pinfunction "2_2") (pintype "passive"))
      (node (ref "C159") (pin "2") (pinfunction "2_2") (pintype "passive"))
      (node (ref "C160") (pin "2") (pinfunction "2_2") (pintype "passive"))
      (node (ref "C161") (pin "2") (pinfunction "2_2") (pintype "passive"))
      (node (ref "C162") (pin "2") (pinfunction "2_2") (pintype "passive"))
      (node (ref "R10") (pin "2") (pinfunction "2_2") (pintype "passive"))
      (node (ref "R12") (pin "1") (pinfunction "1_1") (pintype "passive"))
      (node (ref "R13") (pin "1") (pinfunction "1_1") (pintype "passive"))
      (node (ref "U4") (pin "AA10") (pinfunction "VDDQ_AA10") (pintype "passive"))
      (node (ref "U4") (pin "AA3") (pinfunction "VDDQ_AA3") (pintype "passive"))
      (node (ref "U4") (pin "AA5") (pinfunction "VDDQ_AA5") (pintype "passive"))
      (node (ref "U4") (pin "AA8") (pinfunction "VDDQ_AA8") (pintype "passive"))
      (node (ref "U4") (pin "B10") (pinfunction "VDDQ_B10") (pintype "passive"))
      (node (ref "U4") (pin "B3") (pinfunction "VDDQ_B3") (pintype "passive"))
      (node (ref "U4") (pin "B5") (pinfunction "VDDQ_B5") (pintype "passive"))
      (node (ref "U4") (pin "B8") (pinfunction "VDDQ_B8") (pintype "passive"))
      (node (ref "U4") (pin "D1") (pinfunction "VDDQ_D1") (pintype "passive"))
      (node (ref "U4") (pin "D12") (pinfunction "VDDQ_D12") (pintype "passive"))
      (node (ref "U4") (pin "D5") (pinfunction "VDDQ_D5") (pintype "passive"))
      (node (ref "U4") (pin "D8") (pinfunction "VDDQ_D8") (pintype "passive"))
      (node (ref "U4") (pin "F10") (pinfunction "VDDQ_F10") (pintype "passive"))
      (node (ref "U4") (pin "F3") (pinfunction "VDDQ_F3") (pintype "passive"))
      (node (ref "U4") (pin "U10") (pinfunction "VDDQ_U10") (pintype "passive"))
      (node (ref "U4") (pin "U3") (pinfunction "VDDQ_U3") (pintype "passive"))
      (node (ref "U4") (pin "W1") (pinfunction "VDDQ_W1") (pintype "passive"))
      (node (ref "U4") (pin "W12") (pinfunction "VDDQ_W12") (pintype "passive"))
      (node (ref "U4") (pin "W5") (pinfunction "VDDQ_W5") (pintype "passive"))
      (node (ref "U4") (pin "W8") (pinfunction "VDDQ_W8") (pintype "passive"))
    )
    (net (code "70") (name "unconnected-(U4B-DNU1-PadA1)") (class "Default")
      (node (ref "U4") (pin "A1") (pinfunction "DNU1_A1") (pintype "passive+no_connect"))
    )
    (net (code "71") (name "unconnected-(U4B-DNU2-PadA2)") (class "Default")
      (node (ref "U4") (pin "A2") (pinfunction "DNU2_A2") (pintype "passive+no_connect"))
    )
    (net (code "72") (name "unconnected-(U4B-DNU3-PadA11)") (class "Default")
      (node (ref "U4") (pin "A11") (pinfunction "DNU3_A11") (pintype "passive+no_connect"))
    )
    (net (code "73") (name "unconnected-(U4B-DNU4-PadA12)") (class "Default")
      (node (ref "U4") (pin "A12") (pinfunction "DNU4_A12") (pintype "passive+no_connect"))
    )
    (net (code "74") (name "unconnected-(U4B-DNU5-PadB1)") (class "Default")
      (node (ref "U4") (pin "B1") (pinfunction "DNU5_B1") (pintype "passive+no_connect"))
    )
    (net (code "75") (name "unconnected-(U4B-DNU6-PadB12)") (class "Default")
      (node (ref "U4") (pin "B12") (pinfunction "DNU6_B12") (pintype "passive+no_connect"))
    )
    (net (code "76") (name "unconnected-(U4B-DNU7-PadAA1)") (class "Default")
      (node (ref "U4") (pin "AA1") (pinfunction "DNU7_AA1") (pintype "passive+no_connect"))
    )
    (net (code "77") (name "unconnected-(U4B-DNU8-PadAA12)") (class "Default")
      (node (ref "U4") (pin "AA12") (pinfunction "DNU8_AA12") (pintype "passive+no_connect"))
    )
    (net (code "78") (name "unconnected-(U4B-DNU9-PadAB1)") (class "Default")
      (node (ref "U4") (pin "AB1") (pinfunction "DNU9_AB1") (pintype "passive+no_connect"))
    )
    (net (code "79") (name "unconnected-(U4B-DNU10-PadAB2)") (class "Default")
      (node (ref "U4") (pin "AB2") (pinfunction "DNU10_AB2") (pintype "passive+no_connect"))
    )
    (net (code "80") (name "unconnected-(U4B-DNU11-PadAB11)") (class "Default")
      (node (ref "U4") (pin "AB11") (pinfunction "DNU11_AB11") (pintype "passive+no_connect"))
    )
    (net (code "81") (name "unconnected-(U4B-DNU12-PadAB12)") (class "Default")
      (node (ref "U4") (pin "AB12") (pinfunction "DNU12_AB12") (pintype "passive+no_connect"))
    )
    (net (code "82") (name "unconnected-(U4B-DNU13-PadK8)") (class "Default")
      (node (ref "U4") (pin "K8") (pinfunction "DNU13_K8") (pintype "passive+no_connect"))
    )
    (net (code "83") (name "unconnected-(U4B-DNU14-PadN5)") (class "Default")
      (node (ref "U4") (pin "N5") (pinfunction "DNU14_N5") (pintype "passive+no_connect"))
    )
    (net (code "84") (name "unconnected-(U4B-DNU15-PadK5)") (class "Default")
      (node (ref "U4") (pin "K5") (pinfunction "DNU15_K5") (pintype "passive+no_connect"))
    )
    (net (code "85") (name "unconnected-(U4B-DNU16-PadG11)") (class "Default")
      (node (ref "U4") (pin "G11") (pinfunction "DNU16_G11") (pintype "passive+no_connect"))
    )
    (net (code "86") (name "unconnected-(U4B-DNU17-PadN8)") (class "Default")
      (node (ref "U4") (pin "N8") (pinfunction "DNU17_N8") (pintype "passive+no_connect"))
    )
  )
)
